# RPL_TEMP.net
KiCad netlist of a schematic drawn in Altium Designer
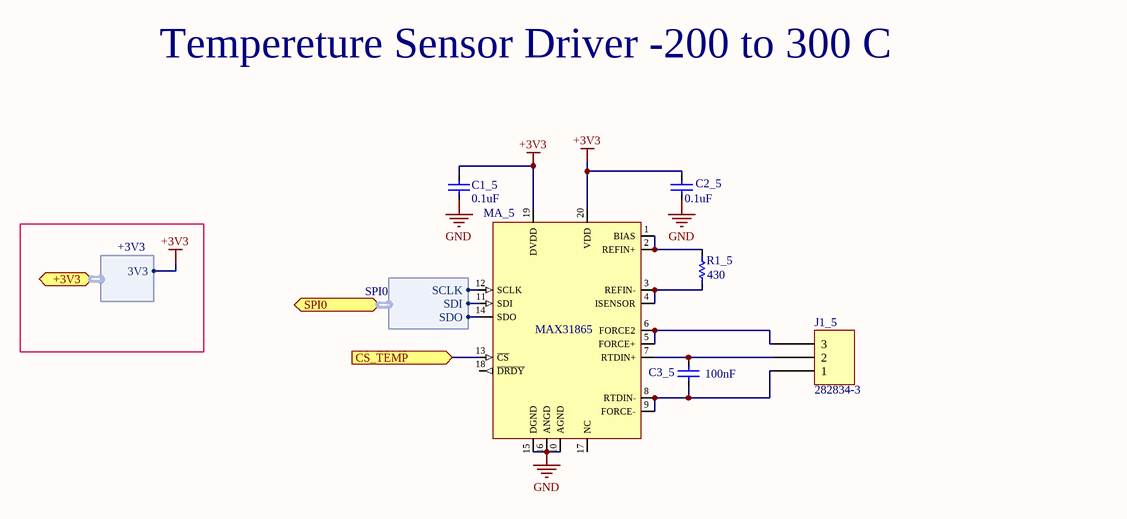
[diagram p0: RPL_TEMP.SchDoc]

(export (version "E")
  (design (tool "Eeschema 10.0.6"))
  (components
    (comp (ref "C1_5")
      (value "0.1uF")
      (footprint "C0805C475K9RACAUTO")
      (fields (field (name "Comment") "Cap"))
      (libsource (lib "Generic_Library") (part "Cap"))
    )
    (comp (ref "C2_5")
      (value "0.1uF")
      (footprint "C0805C475K9RACAUTO")
      (fields (field (name "Comment") "Cap"))
      (libsource (lib "Generic_Library") (part "Cap"))
    )
    (comp (ref "C3_5")
      (value "100nF")
      (footprint "C0805C475K9RACAUTO")
      (fields (field (name "Comment") "Cap"))
      (libsource (lib "Generic_Library") (part "Cap"))
    )
    (comp (ref "J1_5")
      (value "282834-3")
      (footprint "TE 282834-3")
      (description "TERM BLOCK 3POS SIDE ENT 2.54MM")
      (fields (field (name "MANUFACTURER") "TE Connectivity AMP Connectors") (field (name "VOLTAGE") "150V"))
      (libsource (lib "Celestial Library Database") (part "3 Pin"))
    )
    (comp (ref "MA_5")
      (value "MAX31865")
      (footprint "TQFN20-EP-Maxim")
      (libsource (lib "Generic_Library") (part "MAX31865"))
    )
    (comp (ref "R1_5")
      (value "430")
      (footprint "RES 0805")
      (fields (field (name "Comment") "Res"))
      (libsource (lib "Generic_Library") (part "Res"))
    )
  )
  (nets
    (net (code "2") (name "+3V3") (class "Default")
      (node (ref "C1_5") (pin "2") (pinfunction "2_2") (pintype "passive"))
      (node (ref "C2_5") (pin "2") (pinfunction "2_2") (pintype "passive"))
      (node (ref "MA_5") (pin "19") (pinfunction "DVDD_19") (pintype "passive"))
      (node (ref "MA_5") (pin "20") (pinfunction "VDD_20") (pintype "passive"))
    )
    (net (code "3") (name "/CS_TEMP") (class "Default")
      (node (ref "MA_5") (pin "13") (pinfunction "~{CS}_13") (pintype "input"))
    )
    (net (code "4") (name "/SCLK") (class "Default")
      (node (ref "MA_5") (pin "12") (pinfunction "SCLK_12") (pintype "input"))
    )
    (net (code "5") (name "/SDI") (class "Default")
      (node (ref "MA_5") (pin "11") (pinfunction "SDI_11") (pintype "input"))
    )
    (net (code "6") (name "/SDO") (class "Default")
      (node (ref "MA_5") (pin "14") (pinfunction "SDO_14") (pintype "passive"))
    )
    (net (code "9") (name "GND") (class "Default")
      (node (ref "C1_5") (pin "1") (pinfunction "1_1") (pintype "passive"))
      (node (ref "C2_5") (pin "1") (pinfunction "1_1") (pintype "passive"))
      (node (ref "MA_5") (pin "10") (pinfunction "AGND_10") (pintype "passive"))
      (node (ref "MA_5") (pin "15") (pinfunction "DGND_15") (pintype "passive"))
      (node (ref "MA_5") (pin "16") (pinfunction "ANGD_16") (pintype "passive"))
    )
    (net (code "10") (name "Net-(MA_5-BIAS)") (class "Default")
      (node (ref "MA_5") (pin "1") (pinfunction "BIAS_1") (pintype "passive"))
      (node (ref "MA_5") (pin "2") (pinfunction "REFIN+_2") (pintype "passive"))
      (node (ref "R1_5") (pin "2") (pinfunction "2_2") (pintype "passive"))
    )
    (net (code "11") (name "Net-(MA_5-FORCE+)") (class "Default")
      (node (ref "J1_5") (pin "3") (pinfunction "3_3") (pintype "passive"))
      (node (ref "MA_5") (pin "5") (pinfunction "FORCE+_5") (pintype "passive"))
      (node (ref "MA_5") (pin "6") (pinfunction "FORCE2_6") (pintype "passive"))
    )
    (net (code "12") (name "Net-(MA_5-FORCE-)") (class "Default")
      (node (ref "C3_5") (pin "1") (pinfunction "1_1") (pintype "passive"))
      (node (ref "J1_5") (pin "1") (pinfunction "1_1") (pintype "passive"))
      (node (ref "MA_5") (pin "8") (pinfunction "RTDIN-_8") (pintype "passive"))
      (node (ref "MA_5") (pin "9") (pinfunction "FORCE-_9") (pintype "passive"))
    )
    (net (code "13") (name "Net-(MA_5-ISENSOR)") (class "Default")
      (node (ref "MA_5") (pin "3") (pinfunction "REFIN-_3") (pintype "passive"))
      (node (ref "MA_5") (pin "4") (pinfunction "ISENSOR_4") (pintype "passive"))
      (node (ref "R1_5") (pin "1") (pinfunction "1_1") (pintype "passive"))
    )
    (net (code "14") (name "Net-(MA_5-RTDIN+)") (class "Default")
      (node (ref "C3_5") (pin "2") (pinfunction "2_2") (pintype "passive"))
      (node (ref "J1_5") (pin "2") (pinfunction "2_2") (pintype "passive"))
      (node (ref "MA_5") (pin "7") (pinfunction "RTDIN+_7") (pintype "passive"))
    )
    (net (code "15") (name "unconnected-(MA_5-NC-Pad17)") (class "Default")
      (node (ref "MA_5") (pin "17") (pinfunction "NC_17") (pintype "passive"))
    )
    (net (code "16") (name "unconnected-(MA_5-~{DRDY}-Pad18)") (class "Default")
      (node (ref "MA_5") (pin "18") (pinfunction "~{DRDY}_18") (pintype "output"))
    )
  )
)
